# Power-PCB.net
KiCad netlist of a schematic drawn in EAGLE
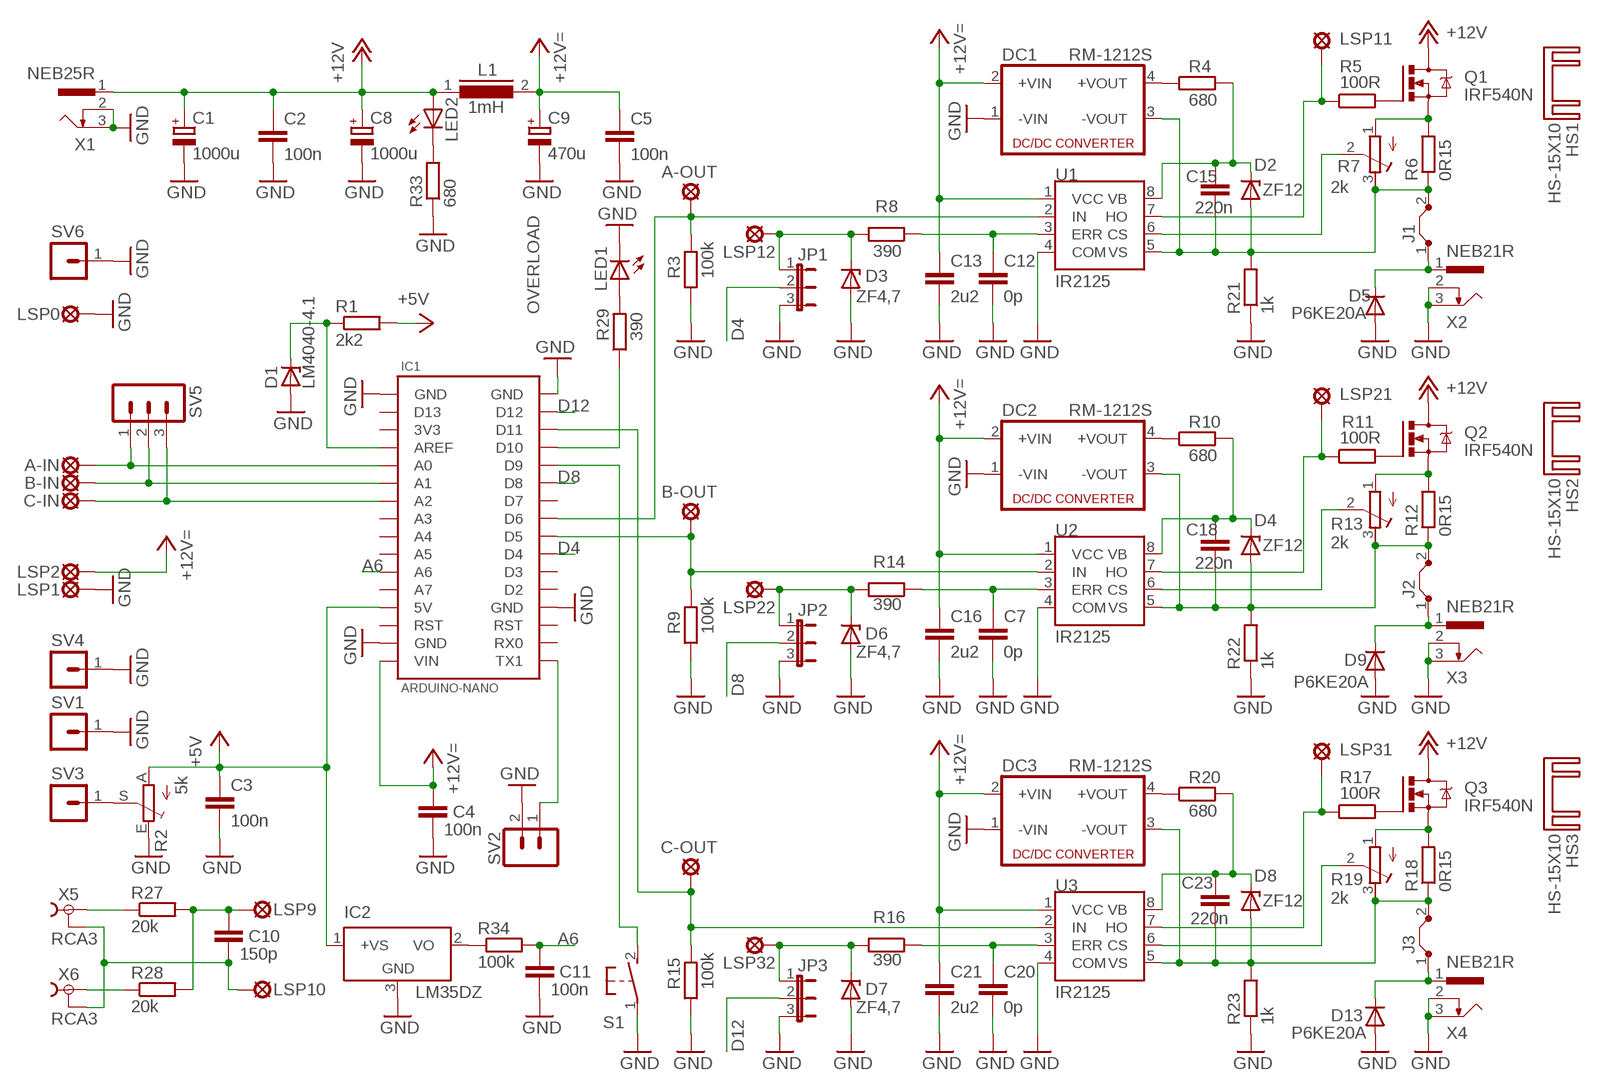
[diagram p0: schematic, sheet 1]

(export (version "E")
  (design (tool "Eeschema 10.0.6"))
  (components
    (comp (ref "A-IN")
      (value "LSP13")
      (footprint "eagle-import:LSP13")
      (libsource (lib "eagle-import") (part "LSP13"))
    )
    (comp (ref "A-OUT")
      (value "LSP13")
      (footprint "eagle-import:LSP13")
      (libsource (lib "eagle-import") (part "LSP13"))
    )
    (comp (ref "B-IN")
      (value "LSP13")
      (footprint "eagle-import:LSP13")
      (libsource (lib "eagle-import") (part "LSP13"))
    )
    (comp (ref "B-OUT")
      (value "LSP13")
      (footprint "eagle-import:LSP13")
      (libsource (lib "eagle-import") (part "LSP13"))
    )
    (comp (ref "C-IN")
      (value "LSP13")
      (footprint "eagle-import:LSP13")
      (libsource (lib "eagle-import") (part "LSP13"))
    )
    (comp (ref "C-OUT")
      (value "LSP13")
      (footprint "eagle-import:LSP13")
      (libsource (lib "eagle-import") (part "LSP13"))
    )
    (comp (ref "C1")
      (value "1000u")
      (footprint "eagle-import:E5-13")
      (libsource (lib "eagle-import") (part "CPOL-EUE5-13"))
    )
    (comp (ref "C2")
      (value "100n")
      (footprint "eagle-import:C050-024X044")
      (libsource (lib "eagle-import") (part "C-EU050-024X044"))
    )
    (comp (ref "C3")
      (value "100n")
      (footprint "eagle-import:C050-024X044")
      (libsource (lib "eagle-import") (part "C-EU050-024X044"))
    )
    (comp (ref "C4")
      (value "100n")
      (footprint "eagle-import:C050-024X044")
      (libsource (lib "eagle-import") (part "C-EU050-024X044"))
    )
    (comp (ref "C5")
      (value "100n")
      (footprint "eagle-import:C050-024X044")
      (libsource (lib "eagle-import") (part "C-EU050-024X044"))
    )
    (comp (ref "C7")
      (value "0p")
      (footprint "eagle-import:C025-024X044")
      (libsource (lib "eagle-import") (part "C-EU025-024X044"))
    )
    (comp (ref "C8")
      (value "1000u")
      (footprint "eagle-import:E5-13")
      (libsource (lib "eagle-import") (part "CPOL-EUE5-13"))
    )
    (comp (ref "C9")
      (value "470u")
      (footprint "eagle-import:E5-10,5")
      (libsource (lib "eagle-import") (part "CPOL-EUE5-10.5"))
    )
    (comp (ref "C10")
      (value "150p")
      (footprint "eagle-import:C025-024X044")
      (libsource (lib "eagle-import") (part "C-EU025-024X044"))
    )
    (comp (ref "C11")
      (value "100n")
      (footprint "eagle-import:C050-024X044")
      (libsource (lib "eagle-import") (part "C-EU050-024X044"))
    )
    (comp (ref "C12")
      (value "0p")
      (footprint "eagle-import:C025-024X044")
      (libsource (lib "eagle-import") (part "C-EU025-024X044"))
    )
    (comp (ref "C13")
      (value "2u2")
      (footprint "eagle-import:C1206")
      (libsource (lib "eagle-import") (part "C-EUC1206"))
    )
    (comp (ref "C15")
      (value "220n")
      (footprint "eagle-import:C050-024X044")
      (libsource (lib "eagle-import") (part "C-EU050-024X044"))
    )
    (comp (ref "C16")
      (value "2u2")
      (footprint "eagle-import:C1206")
      (libsource (lib "eagle-import") (part "C-EUC1206"))
    )
    (comp (ref "C18")
      (value "220n")
      (footprint "eagle-import:C050-024X044")
      (libsource (lib "eagle-import") (part "C-EU050-024X044"))
    )
    (comp (ref "C20")
      (value "0p")
      (footprint "eagle-import:C025-024X044")
      (libsource (lib "eagle-import") (part "C-EU025-024X044"))
    )
    (comp (ref "C21")
      (value "2u2")
      (footprint "eagle-import:C1206")
      (libsource (lib "eagle-import") (part "C-EUC1206"))
    )
    (comp (ref "C23")
      (value "220n")
      (footprint "eagle-import:C050-024X044")
      (libsource (lib "eagle-import") (part "C-EU050-024X044"))
    )
    (comp (ref "D1")
      (value "LM4040-4.1")
      (footprint "eagle-import:TO-92")
      (libsource (lib "eagle-import") (part "LM4040"))
    )
    (comp (ref "D2")
      (value "ZF12")
      (footprint "eagle-import:DO34Z7")
      (libsource (lib "eagle-import") (part "BZX90"))
    )
    (comp (ref "D3")
      (value "ZF4,7")
      (footprint "eagle-import:DO34Z7")
      (libsource (lib "eagle-import") (part "BZX90"))
    )
    (comp (ref "D4")
      (value "ZF12")
      (footprint "eagle-import:DO34Z7")
      (libsource (lib "eagle-import") (part "BZX90"))
    )
    (comp (ref "D5")
      (value "P6KE20A")
      (footprint "eagle-import:C1702-05")
      (libsource (lib "eagle-import") (part "DIODE-C1702-05"))
    )
    (comp (ref "D6")
      (value "ZF4,7")
      (footprint "eagle-import:DO34Z7")
      (libsource (lib "eagle-import") (part "BZX90"))
    )
    (comp (ref "D7")
      (value "ZF4,7")
      (footprint "eagle-import:DO34Z7")
      (libsource (lib "eagle-import") (part "BZX90"))
    )
    (comp (ref "D8")
      (value "ZF12")
      (footprint "eagle-import:DO34Z7")
      (libsource (lib "eagle-import") (part "BZX90"))
    )
    (comp (ref "D9")
      (value "P6KE20A")
      (footprint "eagle-import:C1702-05")
      (libsource (lib "eagle-import") (part "DIODE-C1702-05"))
    )
    (comp (ref "D13")
      (value "P6KE20A")
      (footprint "eagle-import:C1702-05")
      (libsource (lib "eagle-import") (part "DIODE-C1702-05"))
    )
    (comp (ref "DC1")
      (value "RM-1212S")
      (footprint "eagle-import:NME")
      (fields (field (name "MF") "C & D TECHNOLOGIES, INC") (field (name "MPN") "NME1205D"))
      (libsource (lib "eagle-import") (part "NME"))
    )
    (comp (ref "DC2")
      (value "RM-1212S")
      (footprint "eagle-import:NME")
      (fields (field (name "MF") "C & D TECHNOLOGIES, INC") (field (name "MPN") "NME1205D"))
      (libsource (lib "eagle-import") (part "NME"))
    )
    (comp (ref "DC3")
      (value "RM-1212S")
      (footprint "eagle-import:NME")
      (fields (field (name "MF") "C & D TECHNOLOGIES, INC") (field (name "MPN") "NME1205D"))
      (libsource (lib "eagle-import") (part "NME"))
    )
    (comp (ref "HS1")
      (value "HS-15X10")
      (footprint "eagle-import:HEATSINK-TO220-15X10X21")
      (libsource (lib "eagle-import") (part "HS-15X10"))
    )
    (comp (ref "HS2")
      (value "HS-15X10")
      (footprint "eagle-import:HEATSINK-TO220-15X10X21")
      (libsource (lib "eagle-import") (part "HS-15X10"))
    )
    (comp (ref "HS3")
      (value "HS-15X10")
      (footprint "eagle-import:HEATSINK-TO220-15X10X21")
      (libsource (lib "eagle-import") (part "HS-15X10"))
    )
    (comp (ref "IC1")
      (value "ARDUINO-NANO")
      (footprint "eagle-import:ARDUINO-NANO")
      (libsource (lib "eagle-import") (part "ARDUINO-NANO"))
    )
    (comp (ref "IC2")
      (value "LM35DZ")
      (footprint "eagle-import:TO92")
      (libsource (lib "eagle-import") (part "LM35CZ"))
    )
    (comp (ref "J1")
      (value "JUMPER-BRIGDE12MM")
      (footprint "eagle-import:12-THICK-WIRE")
      (libsource (lib "eagle-import") (part "JUMPER-BRIGDE12MM"))
    )
    (comp (ref "J2")
      (value "JUMPER-BRIGDE12MM")
      (footprint "eagle-import:12-THICK-WIRE")
      (libsource (lib "eagle-import") (part "JUMPER-BRIGDE12MM"))
    )
    (comp (ref "J3")
      (value "JUMPER-BRIGDE12MM")
      (footprint "eagle-import:12-THICK-WIRE")
      (libsource (lib "eagle-import") (part "JUMPER-BRIGDE12MM"))
    )
    (comp (ref "JP1")
      (value "JP2E")
      (footprint "eagle-import:JP2")
      (libsource (lib "eagle-import") (part "JP2E"))
    )
    (comp (ref "JP2")
      (value "JP2E")
      (footprint "eagle-import:JP2")
      (libsource (lib "eagle-import") (part "JP2E"))
    )
    (comp (ref "JP3")
      (value "JP2E")
      (footprint "eagle-import:JP2")
      (libsource (lib "eagle-import") (part "JP2E"))
    )
    (comp (ref "L1")
      (value "1mH")
      (footprint "eagle-import:L-09HCP")
      (libsource (lib "eagle-import") (part "L-09HCP"))
    )
    (comp (ref "LED1")
      (value "LED5MM")
      (footprint "eagle-import:LED5MM")
      (libsource (lib "eagle-import") (part "LED5MM"))
    )
    (comp (ref "LED2")
      (value "LED3MM")
      (footprint "eagle-import:LED3MM")
      (libsource (lib "eagle-import") (part "LED3MM"))
    )
    (comp (ref "LSP0")
      (value "LSP13")
      (footprint "eagle-import:LSP13")
      (libsource (lib "eagle-import") (part "LSP13"))
    )
    (comp (ref "LSP1")
      (value "LSP13")
      (footprint "eagle-import:LSP13")
      (libsource (lib "eagle-import") (part "LSP13"))
    )
    (comp (ref "LSP2")
      (value "LSP13")
      (footprint "eagle-import:LSP13")
      (libsource (lib "eagle-import") (part "LSP13"))
    )
    (comp (ref "LSP9")
      (value "LSP13")
      (footprint "eagle-import:LSP13")
      (libsource (lib "eagle-import") (part "LSP13"))
    )
    (comp (ref "LSP10")
      (value "LSP13")
      (footprint "eagle-import:LSP13")
      (libsource (lib "eagle-import") (part "LSP13"))
    )
    (comp (ref "LSP11")
      (value "LSP11")
      (footprint "eagle-import:LSP11")
      (libsource (lib "eagle-import") (part "LSP11"))
    )
    (comp (ref "LSP12")
      (value "LSP11")
      (footprint "eagle-import:LSP11")
      (libsource (lib "eagle-import") (part "LSP11"))
    )
    (comp (ref "LSP21")
      (value "LSP11")
      (footprint "eagle-import:LSP11")
      (libsource (lib "eagle-import") (part "LSP11"))
    )
    (comp (ref "LSP22")
      (value "LSP11")
      (footprint "eagle-import:LSP11")
      (libsource (lib "eagle-import") (part "LSP11"))
    )
    (comp (ref "LSP31")
      (value "LSP11")
      (footprint "eagle-import:LSP11")
      (libsource (lib "eagle-import") (part "LSP11"))
    )
    (comp (ref "LSP32")
      (value "LSP11")
      (footprint "eagle-import:LSP11")
      (libsource (lib "eagle-import") (part "LSP11"))
    )
    (comp (ref "Q1")
      (value "IRF540N")
      (footprint "eagle-import:TO220BV")
      (libsource (lib "eagle-import") (part "IRF540"))
    )
    (comp (ref "Q2")
      (value "IRF540N")
      (footprint "eagle-import:TO220BV")
      (libsource (lib "eagle-import") (part "IRF540"))
    )
    (comp (ref "Q3")
      (value "IRF540N")
      (footprint "eagle-import:TO220BV")
      (libsource (lib "eagle-import") (part "IRF540"))
    )
    (comp (ref "R1")
      (value "2k2")
      (footprint "eagle-import:M1206")
      (libsource (lib "eagle-import") (part "R-EU_M1206"))
    )
    (comp (ref "R2")
      (value "5k")
      (footprint "eagle-import:PT-10")
      (libsource (lib "eagle-import") (part "TRIM_EU-PT10"))
    )
    (comp (ref "R3")
      (value "100k")
      (footprint "eagle-import:0207_10")
      (libsource (lib "eagle-import") (part "R-EU_0207/10"))
    )
    (comp (ref "R4")
      (value "680")
      (footprint "eagle-import:0207_10")
      (libsource (lib "eagle-import") (part "R-EU_0207/10"))
    )
    (comp (ref "R5")
      (value "100R")
      (footprint "eagle-import:M1206")
      (libsource (lib "eagle-import") (part "R-EU_M1206"))
    )
    (comp (ref "R6")
      (value "0R15")
      (footprint "eagle-import:0617V")
      (libsource (lib "eagle-import") (part "R-EU_0617/5V"))
    )
    (comp (ref "R7")
      (value "2k")
      (footprint "eagle-import:RTRIM64W")
      (libsource (lib "eagle-import") (part "R-TRIMM64W"))
    )
    (comp (ref "R8")
      (value "390")
      (footprint "eagle-import:M1206")
      (libsource (lib "eagle-import") (part "R-EU_M1206"))
    )
    (comp (ref "R9")
      (value "100k")
      (footprint "eagle-import:0207_10")
      (libsource (lib "eagle-import") (part "R-EU_0207/10"))
    )
    (comp (ref "R10")
      (value "680")
      (footprint "eagle-import:0207_10")
      (libsource (lib "eagle-import") (part "R-EU_0207/10"))
    )
    (comp (ref "R11")
      (value "100R")
      (footprint "eagle-import:M1206")
      (libsource (lib "eagle-import") (part "R-EU_M1206"))
    )
    (comp (ref "R12")
      (value "0R15")
      (footprint "eagle-import:0617V")
      (libsource (lib "eagle-import") (part "R-EU_0617/5V"))
    )
    (comp (ref "R13")
      (value "2k")
      (footprint "eagle-import:RTRIM64W")
      (libsource (lib "eagle-import") (part "R-TRIMM64W"))
    )
    (comp (ref "R14")
      (value "390")
      (footprint "eagle-import:M1206")
      (libsource (lib "eagle-import") (part "R-EU_M1206"))
    )
    (comp (ref "R15")
      (value "100k")
      (footprint "eagle-import:0207_10")
      (libsource (lib "eagle-import") (part "R-EU_0207/10"))
    )
    (comp (ref "R16")
      (value "390")
      (footprint "eagle-import:M1206")
      (libsource (lib "eagle-import") (part "R-EU_M1206"))
    )
    (comp (ref "R17")
      (value "100R")
      (footprint "eagle-import:M1206")
      (libsource (lib "eagle-import") (part "R-EU_M1206"))
    )
    (comp (ref "R18")
      (value "0R15")
      (footprint "eagle-import:0617V")
      (libsource (lib "eagle-import") (part "R-EU_0617/5V"))
    )
    (comp (ref "R19")
      (value "2k")
      (footprint "eagle-import:RTRIM64W")
      (libsource (lib "eagle-import") (part "R-TRIMM64W"))
    )
    (comp (ref "R20")
      (value "680")
      (footprint "eagle-import:0207_10")
      (libsource (lib "eagle-import") (part "R-EU_0207/10"))
    )
    (comp (ref "R21")
      (value "1k")
      (footprint "eagle-import:0207_2V")
      (libsource (lib "eagle-import") (part "R-EU_0207/2V"))
    )
    (comp (ref "R22")
      (value "1k")
      (footprint "eagle-import:0207_2V")
      (libsource (lib "eagle-import") (part "R-EU_0207/2V"))
    )
    (comp (ref "R23")
      (value "1k")
      (footprint "eagle-import:0207_2V")
      (libsource (lib "eagle-import") (part "R-EU_0207/2V"))
    )
    (comp (ref "R27")
      (value "20k")
      (footprint "eagle-import:M1206")
      (libsource (lib "eagle-import") (part "R-EU_M1206"))
    )
    (comp (ref "R28")
      (value "20k")
      (footprint "eagle-import:M1206")
      (libsource (lib "eagle-import") (part "R-EU_M1206"))
    )
    (comp (ref "R29")
      (value "390")
      (footprint "eagle-import:0207_10")
      (libsource (lib "eagle-import") (part "R-EU_0207/10"))
    )
    (comp (ref "R33")
      (value "680")
      (footprint "eagle-import:M1206")
      (libsource (lib "eagle-import") (part "R-EU_M1206"))
    )
    (comp (ref "R34")
      (value "100k")
      (footprint "eagle-import:M1206")
      (libsource (lib "eagle-import") (part "R-EU_M1206"))
    )
    (comp (ref "S1")
      (value "31-XX")
      (footprint "eagle-import:B3F-31XX")
      (fields (field (name "MPN") "B3F-3100"))
      (libsource (lib "eagle-import") (part "31-XX"))
    )
    (comp (ref "SV1")
      (value "MA01-1")
      (footprint "eagle-import:MA01-1")
      (libsource (lib "eagle-import") (part "MA01-1"))
    )
    (comp (ref "SV2")
      (value "MA02-1")
      (footprint "eagle-import:MA02-1")
      (libsource (lib "eagle-import") (part "MA02-1"))
    )
    (comp (ref "SV3")
      (value "MA01-1")
      (footprint "eagle-import:MA01-1")
      (libsource (lib "eagle-import") (part "MA01-1"))
    )
    (comp (ref "SV4")
      (value "MA01-1")
      (footprint "eagle-import:MA01-1")
      (libsource (lib "eagle-import") (part "MA01-1"))
    )
    (comp (ref "SV5")
      (value "MA03-1")
      (footprint "eagle-import:MA03-1")
      (libsource (lib "eagle-import") (part "MA03-1"))
    )
    (comp (ref "SV6")
      (value "MA01-1")
      (footprint "eagle-import:MA01-1")
      (libsource (lib "eagle-import") (part "MA01-1"))
    )
    (comp (ref "U1")
      (value "IR2125")
      (footprint "eagle-import:DIL08")
      (libsource (lib "eagle-import") (part "IR2125"))
    )
    (comp (ref "U2")
      (value "IR2125")
      (footprint "eagle-import:DIL08")
      (libsource (lib "eagle-import") (part "IR2125"))
    )
    (comp (ref "U3")
      (value "IR2125")
      (footprint "eagle-import:DIL08")
      (libsource (lib "eagle-import") (part "IR2125"))
    )
    (comp (ref "X1")
      (value "NEB25R")
      (footprint "eagle-import:NEB21R")
      (fields (field (name "MPN") "NEB 21 R"))
      (libsource (lib "eagle-import") (part "NEB21R"))
    )
    (comp (ref "X2")
      (value "NEB21R")
      (footprint "eagle-import:NEB21R")
      (fields (field (name "MPN") "NEB 21 R"))
      (libsource (lib "eagle-import") (part "NEB21R"))
    )
    (comp (ref "X3")
      (value "NEB21R")
      (footprint "eagle-import:NEB21R")
      (fields (field (name "MPN") "NEB 21 R"))
      (libsource (lib "eagle-import") (part "NEB21R"))
    )
    (comp (ref "X4")
      (value "NEB21R")
      (footprint "eagle-import:NEB21R")
      (fields (field (name "MPN") "NEB 21 R"))
      (libsource (lib "eagle-import") (part "NEB21R"))
    )
    (comp (ref "X5")
      (value "RCA3")
      (footprint "eagle-import:RCA3")
      (libsource (lib "eagle-import") (part "RCA3"))
    )
    (comp (ref "X6")
      (value "RCA3")
      (footprint "eagle-import:RCA3")
      (libsource (lib "eagle-import") (part "RCA3"))
    )
  )
  (nets
    (net (code "1") (name "+5V") (class "Default")
      (node (ref "C3") (pin "1") (pinfunction "1_1") (pintype "passive"))
      (node (ref "IC1") (pin "+5V") (pinfunction "5V_+5V") (pintype "bidirectional"))
      (node (ref "IC2") (pin "1") (pinfunction "+VS_1") (pintype "input"))
      (node (ref "R1") (pin "2") (pinfunction "2_2") (pintype "passive"))
      (node (ref "R2") (pin "A") (pinfunction "A_A") (pintype "passive"))
    )
    (net (code "2") (name "+12V") (class "Default")
      (node (ref "C1") (pin "+") (pinfunction "+_+") (pintype "passive"))
      (node (ref "C2") (pin "1") (pinfunction "1_1") (pintype "passive"))
      (node (ref "C8") (pin "+") (pinfunction "+_+") (pintype "passive"))
      (node (ref "L1") (pin "1") (pinfunction "1_1") (pintype "passive"))
      (node (ref "LED2") (pin "A") (pinfunction "A_A") (pintype "passive"))
      (node (ref "Q1") (pin "D") (pinfunction "D_D") (pintype "passive"))
      (node (ref "Q2") (pin "D") (pinfunction "D_D") (pintype "passive"))
      (node (ref "Q3") (pin "D") (pinfunction "D_D") (pintype "passive"))
      (node (ref "X1") (pin "1") (pinfunction "1_1") (pintype "passive"))
    )
    (net (code "3") (name "+12V=") (class "Default")
      (node (ref "C13") (pin "1") (pinfunction "1_1") (pintype "passive"))
      (node (ref "C16") (pin "1") (pinfunction "1_1") (pintype "passive"))
      (node (ref "C21") (pin "1") (pinfunction "1_1") (pintype "passive"))
      (node (ref "C4") (pin "1") (pinfunction "1_1") (pintype "passive"))
      (node (ref "C5") (pin "1") (pinfunction "1_1") (pintype "passive"))
      (node (ref "C9") (pin "+") (pinfunction "+_+") (pintype "passive"))
      (node (ref "DC1") (pin "2") (pinfunction "+VIN_2") (pintype "passive"))
      (node (ref "DC2") (pin "2") (pinfunction "+VIN_2") (pintype "passive"))
      (node (ref "DC3") (pin "2") (pinfunction "+VIN_2") (pintype "passive"))
      (node (ref "IC1") (pin "VIN") (pinfunction "VIN_VIN") (pintype "power_in"))
      (node (ref "L1") (pin "2") (pinfunction "2_2") (pintype "passive"))
      (node (ref "LSP2") (pin "MP") (pinfunction "MP_MP") (pintype "passive"))
      (node (ref "U1") (pin "1") (pinfunction "VCC_1") (pintype "power_in"))
      (node (ref "U2") (pin "1") (pinfunction "VCC_1") (pintype "power_in"))
      (node (ref "U3") (pin "1") (pinfunction "VCC_1") (pintype "power_in"))
    )
    (net (code "4") (name "/3V3") (class "Default")
      (node (ref "IC1") (pin "3V3") (pinfunction "3V3_3V3") (pintype "power_in"))
    )
    (net (code "5") (name "/A6") (class "Default")
      (node (ref "C11") (pin "1") (pinfunction "1_1") (pintype "passive"))
      (node (ref "IC1") (pin "A6") (pinfunction "A6_A6") (pintype "bidirectional"))
      (node (ref "R34") (pin "2") (pinfunction "2_2") (pintype "passive"))
    )
    (net (code "6") (name "/D4") (class "Default")
      (node (ref "IC1") (pin "D4") (pinfunction "D4_D4") (pintype "bidirectional"))
      (node (ref "JP1") (pin "2") (pinfunction "2_2") (pintype "passive"))
    )
    (net (code "7") (name "/D8") (class "Default")
      (node (ref "IC1") (pin "D8") (pinfunction "D8_D8") (pintype "bidirectional"))
      (node (ref "JP2") (pin "2") (pinfunction "2_2") (pintype "passive"))
    )
    (net (code "8") (name "/D12") (class "Default")
      (node (ref "IC1") (pin "D12") (pinfunction "D12_D12") (pintype "bidirectional"))
      (node (ref "JP3") (pin "2") (pinfunction "2_2") (pintype "passive"))
    )
    (net (code "9") (name "/OVERLOAD") (class "Default")
      (node (ref "IC1") (pin "D10") (pinfunction "D10_D10") (pintype "bidirectional"))
      (node (ref "R29") (pin "1") (pinfunction "1_1") (pintype "passive"))
    )
    (net (code "10") (name "GND") (class "Default")
      (node (ref "C1") (pin "-") (pinfunction "-_-") (pintype "passive"))
      (node (ref "C11") (pin "2") (pinfunction "2_2") (pintype "passive"))
      (node (ref "C12") (pin "2") (pinfunction "2_2") (pintype "passive"))
      (node (ref "C13") (pin "2") (pinfunction "2_2") (pintype "passive"))
      (node (ref "C16") (pin "2") (pinfunction "2_2") (pintype "passive"))
      (node (ref "C2") (pin "2") (pinfunction "2_2") (pintype "passive"))
      (node (ref "C20") (pin "2") (pinfunction "2_2") (pintype "passive"))
      (node (ref "C21") (pin "2") (pinfunction "2_2") (pintype "passive"))
      (node (ref "C3") (pin "2") (pinfunction "2_2") (pintype "passive"))
      (node (ref "C4") (pin "2") (pinfunction "2_2") (pintype "passive"))
      (node (ref "C5") (pin "2") (pinfunction "2_2") (pintype "passive"))
      (node (ref "C7") (pin "2") (pinfunction "2_2") (pintype "passive"))
      (node (ref "C8") (pin "-") (pinfunction "-_-") (pintype "passive"))
      (node (ref "C9") (pin "-") (pinfunction "-_-") (pintype "passive"))
      (node (ref "D1") (pin "3") (pinfunction "A_3") (pintype "passive"))
      (node (ref "D13") (pin "A") (pinfunction "A_A") (pintype "passive"))
      (node (ref "D3") (pin "A") (pinfunction "A_A") (pintype "passive"))
      (node (ref "D5") (pin "A") (pinfunction "A_A") (pintype "passive"))
      (node (ref "D6") (pin "A") (pinfunction "A_A") (pintype "passive"))
      (node (ref "D7") (pin "A") (pinfunction "A_A") (pintype "passive"))
      (node (ref "D9") (pin "A") (pinfunction "A_A") (pintype "passive"))
      (node (ref "DC1") (pin "1") (pinfunction "-VIN_1") (pintype "passive"))
      (node (ref "DC2") (pin "1") (pinfunction "-VIN_1") (pintype "passive"))
      (node (ref "DC3") (pin "1") (pinfunction "-VIN_1") (pintype "passive"))
      (node (ref "IC1") (pin "GND") (pinfunction "GND_GND") (pintype "power_in"))
      (node (ref "IC1") (pin "GND1") (pinfunction "GND_GND1") (pintype "power_in"))
      (node (ref "IC1") (pin "GND2") (pinfunction "GND_GND2") (pintype "power_in"))
      (node (ref "IC1") (pin "GND3") (pinfunction "GND_GND3") (pintype "power_in"))
      (node (ref "IC2") (pin "3") (pinfunction "GND_3") (pintype "power_in"))
      (node (ref "JP1") (pin "3") (pinfunction "3_3") (pintype "passive"))
      (node (ref "JP2") (pin "3") (pinfunction "3_3") (pintype "passive"))
      (node (ref "JP3") (pin "3") (pinfunction "3_3") (pintype "passive"))
      (node (ref "LED1") (pin "K") (pinfunction "C_K") (pintype "passive"))
      (node (ref "LSP0") (pin "MP") (pinfunction "MP_MP") (pintype "passive"))
      (node (ref "LSP1") (pin "MP") (pinfunction "MP_MP") (pintype "passive"))
      (node (ref "R15") (pin "1") (pinfunction "1_1") (pintype "passive"))
      (node (ref "R2") (pin "E") (pinfunction "E_E") (pintype "passive"))
      (node (ref "R21") (pin "1") (pinfunction "1_1") (pintype "passive"))
      (node (ref "R22") (pin "1") (pinfunction "1_1") (pintype "passive"))
      (node (ref "R23") (pin "1") (pinfunction "1_1") (pintype "passive"))
      (node (ref "R3") (pin "1") (pinfunction "1_1") (pintype "passive"))
      (node (ref "R33") (pin "1") (pinfunction "1_1") (pintype "passive"))
      (node (ref "R9") (pin "1") (pinfunction "1_1") (pintype "passive"))
      (node (ref "S1") (pin "1") (pinfunction "P_1") (pintype "passive"))
      (node (ref "SV1") (pin "1") (pinfunction "1_1") (pintype "passive"))
      (node (ref "SV2") (pin "2") (pinfunction "2_2") (pintype "passive"))
      (node (ref "SV4") (pin "1") (pinfunction "1_1") (pintype "passive"))
      (node (ref "SV6") (pin "1") (pinfunction "1_1") (pintype "passive"))
      (node (ref "U1") (pin "4") (pinfunction "COM_4") (pintype "power_in"))
      (node (ref "U2") (pin "4") (pinfunction "COM_4") (pintype "power_in"))
      (node (ref "U3") (pin "4") (pinfunction "COM_4") (pintype "power_in"))
      (node (ref "X1") (pin "2") (pinfunction "2_2") (pintype "passive"))
      (node (ref "X1") (pin "3") (pinfunction "3_3") (pintype "passive"))
      (node (ref "X2") (pin "2") (pinfunction "2_2") (pintype "passive"))
      (node (ref "X2") (pin "3") (pinfunction "3_3") (pintype "passive"))
      (node (ref "X3") (pin "2") (pinfunction "2_2") (pintype "passive"))
      (node (ref "X3") (pin "3") (pinfunction "3_3") (pintype "passive"))
      (node (ref "X4") (pin "2") (pinfunction "2_2") (pintype "passive"))
      (node (ref "X4") (pin "3") (pinfunction "3_3") (pintype "passive"))
    )
    (net (code "11") (name "Net-(A-IN-PadMP)") (class "Default")
      (node (ref "A-IN") (pin "MP") (pinfunction "MP_MP") (pintype "passive"))
      (node (ref "IC1") (pin "A0") (pinfunction "A0_A0") (pintype "bidirectional"))
      (node (ref "SV5") (pin "1") (pinfunction "1_1") (pintype "passive"))
    )
    (net (code "12") (name "Net-(B-IN-PadMP)") (class "Default")
      (node (ref "B-IN") (pin "MP") (pinfunction "MP_MP") (pintype "passive"))
      (node (ref "IC1") (pin "A1") (pinfunction "A1_A1") (pintype "bidirectional"))
      (node (ref "SV5") (pin "2") (pinfunction "2_2") (pintype "passive"))
    )
    (net (code "13") (name "Net-(C-IN-PadMP)") (class "Default")
      (node (ref "C-IN") (pin "MP") (pinfunction "MP_MP") (pintype "passive"))
      (node (ref "IC1") (pin "A2") (pinfunction "A2_A2") (pintype "bidirectional"))
      (node (ref "SV5") (pin "3") (pinfunction "3_3") (pintype "passive"))
    )
    (net (code "14") (name "Net-(C10-Pad1)") (class "Default")
      (node (ref "C10") (pin "1") (pinfunction "1_1") (pintype "passive"))
      (node (ref "LSP9") (pin "MP") (pinfunction "MP_MP") (pintype "passive"))
      (node (ref "R27") (pin "2") (pinfunction "2_2") (pintype "passive"))
      (node (ref "R28") (pin "2") (pinfunction "2_2") (pintype "passive"))
    )
    (net (code "15") (name "Net-(C10-Pad2)") (class "Default")
      (node (ref "C10") (pin "2") (pinfunction "2_2") (pintype "passive"))
      (node (ref "LSP10") (pin "MP") (pinfunction "MP_MP") (pintype "passive"))
      (node (ref "X5") (pin "2") (pinfunction "2_2") (pintype "passive"))
      (node (ref "X5") (pin "2@1") (pinfunction "2_2@1") (pintype "passive"))
      (node (ref "X5") (pin "2@2") (pinfunction "2_2@2") (pintype "passive"))
      (node (ref "X6") (pin "2") (pinfunction "2_2") (pintype "passive"))
      (node (ref "X6") (pin "2@1") (pinfunction "2_2@1") (pintype "passive"))
      (node (ref "X6") (pin "2@2") (pinfunction "2_2@2") (pintype "passive"))
    )
    (net (code "16") (name "Net-(D1-C)") (class "Default")
      (node (ref "D1") (pin "2") (pinfunction "C_2") (pintype "passive"))
      (node (ref "IC1") (pin "AREF") (pinfunction "AREF_AREF") (pintype "input"))
      (node (ref "R1") (pin "1") (pinfunction "1_1") (pintype "passive"))
    )
    (net (code "17") (name "Net-(D3-PadC)") (class "Default")
      (node (ref "D3") (pin "C") (pinfunction "C_C") (pintype "passive"))
      (node (ref "JP1") (pin "1") (pinfunction "1_1") (pintype "passive"))
      (node (ref "LSP12") (pin "MP") (pinfunction "MP_MP") (pintype "passive"))
      (node (ref "R8") (pin "2") (pinfunction "2_2") (pintype "passive"))
    )
    (net (code "18") (name "Net-(D5-PadC)") (class "Default")
      (node (ref "D5") (pin "C") (pinfunction "C_C") (pintype "passive"))
      (node (ref "J1") (pin "1") (pinfunction "1_1") (pintype "passive"))
      (node (ref "X2") (pin "1") (pinfunction "1_1") (pintype "passive"))
    )
    (net (code "19") (name "Net-(D6-PadC)") (class "Default")
      (node (ref "D6") (pin "C") (pinfunction "C_C") (pintype "passive"))
      (node (ref "JP2") (pin "1") (pinfunction "1_1") (pintype "passive"))
      (node (ref "LSP22") (pin "MP") (pinfunction "MP_MP") (pintype "passive"))
      (node (ref "R14") (pin "2") (pinfunction "2_2") (pintype "passive"))
    )
    (net (code "20") (name "Net-(D7-PadC)") (class "Default")
      (node (ref "D7") (pin "C") (pinfunction "C_C") (pintype "passive"))
      (node (ref "JP3") (pin "1") (pinfunction "1_1") (pintype "passive"))
      (node (ref "LSP32") (pin "MP") (pinfunction "MP_MP") (pintype "passive"))
      (node (ref "R16") (pin "2") (pinfunction "2_2") (pintype "passive"))
    )
    (net (code "21") (name "Net-(D9-PadC)") (class "Default")
      (node (ref "D9") (pin "C") (pinfunction "C_C") (pintype "passive"))
      (node (ref "J2") (pin "1") (pinfunction "1_1") (pintype "passive"))
      (node (ref "X3") (pin "1") (pinfunction "1_1") (pintype "passive"))
    )
    (net (code "22") (name "Net-(D13-PadC)") (class "Default")
      (node (ref "D13") (pin "C") (pinfunction "C_C") (pintype "passive"))
      (node (ref "J3") (pin "1") (pinfunction "1_1") (pintype "passive"))
      (node (ref "X4") (pin "1") (pinfunction "1_1") (pintype "passive"))
    )
    (net (code "23") (name "Net-(DC1-+VOUT)") (class "Default")
      (node (ref "DC1") (pin "4") (pinfunction "+VOUT_4") (pintype "passive"))
      (node (ref "R4") (pin "1") (pinfunction "1_1") (pintype "passive"))
    )
    (net (code "24") (name "Net-(DC1--VOUT)") (class "Default")
      (node (ref "C15") (pin "2") (pinfunction "2_2") (pintype "passive"))
      (node (ref "D2") (pin "A") (pinfunction "A_A") (pintype "passive"))
      (node (ref "DC1") (pin "3") (pinfunction "-VOUT_3") (pintype "passive"))
      (node (ref "J1") (pin "2") (pinfunction "2_2") (pintype "passive"))
      (node (ref "R21") (pin "2") (pinfunction "2_2") (pintype "passive"))
      (node (ref "R6") (pin "1") (pinfunction "1_1") (pintype "passive"))
      (node (ref "R7") (pin "3") (pinfunction "E_3") (pintype "passive"))
      (node (ref "U1") (pin "5") (pinfunction "VS_5") (pintype "power_in"))
    )
    (net (code "25") (name "Net-(DC2-+VOUT)") (class "Default")
      (node (ref "DC2") (pin "4") (pinfunction "+VOUT_4") (pintype "passive"))
      (node (ref "R10") (pin "1") (pinfunction "1_1") (pintype "passive"))
    )
    (net (code "26") (name "Net-(DC2--VOUT)") (class "Default")
      (node (ref "C18") (pin "2") (pinfunction "2_2") (pintype "passive"))
      (node (ref "D4") (pin "A") (pinfunction "A_A") (pintype "passive"))
      (node (ref "DC2") (pin "3") (pinfunction "-VOUT_3") (pintype "passive"))
      (node (ref "J2") (pin "2") (pinfunction "2_2") (pintype "passive"))
      (node (ref "R12") (pin "1") (pinfunction "1_1") (pintype "passive"))
      (node (ref "R13") (pin "3") (pinfunction "E_3") (pintype "passive"))
      (node (ref "R22") (pin "2") (pinfunction "2_2") (pintype "passive"))
      (node (ref "U2") (pin "5") (pinfunction "VS_5") (pintype "power_in"))
    )
    (net (code "27") (name "Net-(DC3-+VOUT)") (class "Default")
      (node (ref "DC3") (pin "4") (pinfunction "+VOUT_4") (pintype "passive"))
      (node (ref "R20") (pin "1") (pinfunction "1_1") (pintype "passive"))
    )
    (net (code "28") (name "Net-(DC3--VOUT)") (class "Default")
      (node (ref "C23") (pin "2") (pinfunction "2_2") (pintype "passive"))
      (node (ref "D8") (pin "A") (pinfunction "A_A") (pintype "passive"))
      (node (ref "DC3") (pin "3") (pinfunction "-VOUT_3") (pintype "passive"))
      (node (ref "J3") (pin "2") (pinfunction "2_2") (pintype "passive"))
      (node (ref "R18") (pin "1") (pinfunction "1_1") (pintype "passive"))
      (node (ref "R19") (pin "3") (pinfunction "E_3") (pintype "passive"))
      (node (ref "R23") (pin "2") (pinfunction "2_2") (pintype "passive"))
      (node (ref "U3") (pin "5") (pinfunction "VS_5") (pintype "power_in"))
    )
    (net (code "29") (name "Net-(IC1-PadTX1)") (class "Default")
      (node (ref "IC1") (pin "TX1") (pinfunction "TX1_TX1") (pintype "bidirectional"))
      (node (ref "SV2") (pin "1") (pinfunction "1_1") (pintype "passive"))
    )
    (net (code "30") (name "Net-(IC2-VO)") (class "Default")
      (node (ref "IC2") (pin "2") (pinfunction "VO_2") (pintype "input"))
      (node (ref "R34") (pin "1") (pinfunction "1_1") (pintype "passive"))
    )
    (net (code "31") (name "Net-(LED1-PadA)") (class "Default")
      (node (ref "LED1") (pin "A") (pinfunction "A_A") (pintype "passive"))
      (node (ref "R29") (pin "2") (pinfunction "2_2") (pintype "passive"))
    )
    (net (code "32") (name "Net-(LED2-C)") (class "Default")
      (node (ref "LED2") (pin "K") (pinfunction "C_K") (pintype "passive"))
      (node (ref "R33") (pin "2") (pinfunction "2_2") (pintype "passive"))
    )
    (net (code "33") (name "Net-(Q1-PadG)") (class "Default")
      (node (ref "Q1") (pin "G") (pinfunction "G_G") (pintype "passive"))
      (node (ref "R5") (pin "2") (pinfunction "2_2") (pintype "passive"))
    )
    (net (code "34") (name "Net-(Q2-PadG)") (class "Default")
      (node (ref "Q2") (pin "G") (pinfunction "G_G") (pintype "passive"))
      (node (ref "R11") (pin "2") (pinfunction "2_2") (pintype "passive"))
    )
    (net (code "35") (name "Net-(Q3-PadG)") (class "Default")
      (node (ref "Q3") (pin "G") (pinfunction "G_G") (pintype "passive"))
      (node (ref "R17") (pin "2") (pinfunction "2_2") (pintype "passive"))
    )
    (net (code "36") (name "Net-(R2-PadS)") (class "Default")
      (node (ref "R2") (pin "S") (pinfunction "S_S") (pintype "passive"))
      (node (ref "SV3") (pin "1") (pinfunction "1_1") (pintype "passive"))
    )
    (net (code "37") (name "Net-(R7-A)") (class "Default")
      (node (ref "Q1") (pin "S") (pinfunction "S_S") (pintype "passive"))
      (node (ref "R6") (pin "2") (pinfunction "2_2") (pintype "passive"))
      (node (ref "R7") (pin "1") (pinfunction "A_1") (pintype "passive"))
    )
    (net (code "38") (name "Net-(R7-S)") (class "Default")
      (node (ref "R7") (pin "2") (pinfunction "S_2") (pintype "passive"))
      (node (ref "U1") (pin "6") (pinfunction "CS_6") (pintype "input"))
    )
    (net (code "39") (name "Net-(R13-A)") (class "Default")
      (node (ref "Q2") (pin "S") (pinfunction "S_S") (pintype "passive"))
      (node (ref "R12") (pin "2") (pinfunction "2_2") (pintype "passive"))
      (node (ref "R13") (pin "1") (pinfunction "A_1") (pintype "passive"))
    )
    (net (code "40") (name "Net-(R13-S)") (class "Default")
      (node (ref "R13") (pin "2") (pinfunction "S_2") (pintype "passive"))
      (node (ref "U2") (pin "6") (pinfunction "CS_6") (pintype "input"))
    )
    (net (code "41") (name "Net-(R19-A)") (class "Default")
      (node (ref "Q3") (pin "S") (pinfunction "S_S") (pintype "passive"))
      (node (ref "R18") (pin "2") (pinfunction "2_2") (pintype "passive"))
      (node (ref "R19") (pin "1") (pinfunction "A_1") (pintype "passive"))
    )
    (net (code "42") (name "Net-(R19-S)") (class "Default")
      (node (ref "R19") (pin "2") (pinfunction "S_2") (pintype "passive"))
      (node (ref "U3") (pin "6") (pinfunction "CS_6") (pintype "input"))
    )
    (net (code "43") (name "Net-(R27-Pad1)") (class "Default")
      (node (ref "R27") (pin "1") (pinfunction "1_1") (pintype "passive"))
      (node (ref "X5") (pin "1") (pinfunction "1_1") (pintype "passive"))
    )
    (net (code "44") (name "Net-(R28-Pad1)") (class "Default")
      (node (ref "R28") (pin "1") (pinfunction "1_1") (pintype "passive"))
      (node (ref "X6") (pin "1") (pinfunction "1_1") (pintype "passive"))
    )
    (net (code "45") (name "Net-(S1-S)") (class "Default")
      (node (ref "IC1") (pin "D9") (pinfunction "D9_D9") (pintype "bidirectional"))
      (node (ref "S1") (pin "2") (pinfunction "S_2") (pintype "passive"))
    )
    (net (code "46") (name "Net-(U1-ERR)") (class "Default")
      (node (ref "C12") (pin "1") (pinfunction "1_1") (pintype "passive"))
      (node (ref "R8") (pin "1") (pinfunction "1_1") (pintype "passive"))
      (node (ref "U1") (pin "3") (pinfunction "ERR_3") (pintype "input"))
    )
    (net (code "47") (name "Net-(U1-HO)") (class "Default")
      (node (ref "LSP11") (pin "MP") (pinfunction "MP_MP") (pintype "passive"))
      (node (ref "R5") (pin "1") (pinfunction "1_1") (pintype "passive"))
      (node (ref "U1") (pin "7") (pinfunction "HO_7") (pintype "output"))
    )
    (net (code "48") (name "Net-(U1-IN)") (class "Default")
      (node (ref "A-OUT") (pin "MP") (pinfunction "MP_MP") (pintype "passive"))
      (node (ref "IC1") (pin "D6") (pinfunction "D6_D6") (pintype "bidirectional"))
      (node (ref "R3") (pin "2") (pinfunction "2_2") (pintype "passive"))
      (node (ref "U1") (pin "2") (pinfunction "IN_2") (pintype "input"))
    )
    (net (code "49") (name "Net-(U1-VB)") (class "Default")
      (node (ref "C15") (pin "1") (pinfunction "1_1") (pintype "passive"))
      (node (ref "D2") (pin "C") (pinfunction "C_C") (pintype "passive"))
      (node (ref "R4") (pin "2") (pinfunction "2_2") (pintype "passive"))
      (node (ref "U1") (pin "8") (pinfunction "VB_8") (pintype "power_in"))
    )
    (net (code "50") (name "Net-(U2-ERR)") (class "Default")
      (node (ref "C7") (pin "1") (pinfunction "1_1") (pintype "passive"))
      (node (ref "R14") (pin "1") (pinfunction "1_1") (pintype "passive"))
      (node (ref "U2") (pin "3") (pinfunction "ERR_3") (pintype "input"))
    )
    (net (code "51") (name "Net-(U2-HO)") (class "Default")
      (node (ref "LSP21") (pin "MP") (pinfunction "MP_MP") (pintype "passive"))
      (node (ref "R11") (pin "1") (pinfunction "1_1") (pintype "passive"))
      (node (ref "U2") (pin "7") (pinfunction "HO_7") (pintype "output"))
    )
    (net (code "52") (name "Net-(U2-IN)") (class "Default")
      (node (ref "B-OUT") (pin "MP") (pinfunction "MP_MP") (pintype "passive"))
      (node (ref "IC1") (pin "D5") (pinfunction "D5_D5") (pintype "bidirectional"))
      (node (ref "R9") (pin "2") (pinfunction "2_2") (pintype "passive"))
      (node (ref "U2") (pin "2") (pinfunction "IN_2") (pintype "input"))
    )
    (net (code "53") (name "Net-(U2-VB)") (class "Default")
      (node (ref "C18") (pin "1") (pinfunction "1_1") (pintype "passive"))
      (node (ref "D4") (pin "C") (pinfunction "C_C") (pintype "passive"))
      (node (ref "R10") (pin "2") (pinfunction "2_2") (pintype "passive"))
      (node (ref "U2") (pin "8") (pinfunction "VB_8") (pintype "power_in"))
    )
    (net (code "54") (name "Net-(U3-ERR)") (class "Default")
      (node (ref "C20") (pin "1") (pinfunction "1_1") (pintype "passive"))
      (node (ref "R16") (pin "1") (pinfunction "1_1") (pintype "passive"))
      (node (ref "U3") (pin "3") (pinfunction "ERR_3") (pintype "input"))
    )
    (net (code "55") (name "Net-(U3-HO)") (class "Default")
      (node (ref "LSP31") (pin "MP") (pinfunction "MP_MP") (pintype "passive"))
      (node (ref "R17") (pin "1") (pinfunction "1_1") (pintype "passive"))
      (node (ref "U3") (pin "7") (pinfunction "HO_7") (pintype "output"))
    )
    (net (code "56") (name "Net-(U3-IN)") (class "Default")
      (node (ref "C-OUT") (pin "MP") (pinfunction "MP_MP") (pintype "passive"))
      (node (ref "IC1") (pin "D11") (pinfunction "D11_D11") (pintype "bidirectional"))
      (node (ref "R15") (pin "2") (pinfunction "2_2") (pintype "passive"))
      (node (ref "U3") (pin "2") (pinfunction "IN_2") (pintype "input"))
    )
    (net (code "57") (name "Net-(U3-VB)") (class "Default")
      (node (ref "C23") (pin "1") (pinfunction "1_1") (pintype "passive"))
      (node (ref "D8") (pin "C") (pinfunction "C_C") (pintype "passive"))
      (node (ref "R20") (pin "2") (pinfunction "2_2") (pintype "passive"))
      (node (ref "U3") (pin "8") (pinfunction "VB_8") (pintype "power_in"))
    )
    (net (code "58") (name "unconnected-(IC1-PadA3)") (class "Default")
      (node (ref "IC1") (pin "A3") (pinfunction "A3_A3") (pintype "bidirectional"))
    )
    (net (code "59") (name "unconnected-(IC1-PadA4)") (class "Default")
      (node (ref "IC1") (pin "A4") (pinfunction "A4_A4") (pintype "bidirectional"))
    )
    (net (code "60") (name "unconnected-(IC1-PadA5)") (class "Default")
      (node (ref "IC1") (pin "A5") (pinfunction "A5_A5") (pintype "bidirectional"))
    )
    (net (code "61") (name "unconnected-(IC1-PadA7)") (class "Default")
      (node (ref "IC1") (pin "A7") (pinfunction "A7_A7") (pintype "bidirectional"))
    )
    (net (code "62") (name "unconnected-(IC1-PadD2)") (class "Default")
      (node (ref "IC1") (pin "D2") (pinfunction "D2_D2") (pintype "bidirectional"))
    )
    (net (code "63") (name "unconnected-(IC1-PadD3)") (class "Default")
      (node (ref "IC1") (pin "D3") (pinfunction "D3_D3") (pintype "bidirectional"))
    )
    (net (code "64") (name "unconnected-(IC1-PadD7)") (class "Default")
      (node (ref "IC1") (pin "D7") (pinfunction "D7_D7") (pintype "bidirectional"))
    )
    (net (code "65") (name "unconnected-(IC1-PadD13)") (class "Default")
      (node (ref "IC1") (pin "D13") (pinfunction "D13_D13") (pintype "bidirectional"))
    )
    (net (code "66") (name "unconnected-(IC1-PadRX0)") (class "Default")
      (node (ref "IC1") (pin "RX0") (pinfunction "RX0_RX0") (pintype "bidirectional"))
    )
    (net (code "67") (name "unconnected-(IC1-RST-PadRESET)") (class "Default")
      (node (ref "IC1") (pin "RESET") (pinfunction "RST_RESET") (pintype "input"))
    )
    (net (code "68") (name "unconnected-(IC1-RST-PadRESET1)") (class "Default")
      (node (ref "IC1") (pin "RESET1") (pinfunction "RST_RESET1") (pintype "input"))
    )
  )
)
